# schemat.net
KiCad netlist of a schematic drawn in Altium Designer
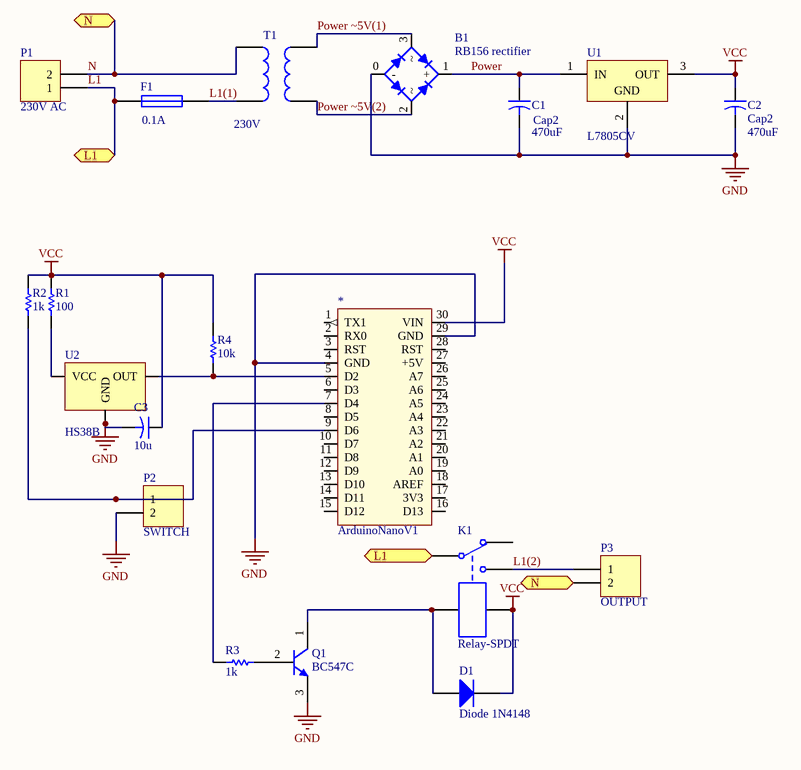
[diagram p0: schemat.SchDoc]

(export (version "E")
  (design (tool "Eeschema 10.0.6"))
  (components
    (comp (ref "*")
      (value "ArduinoNanoV1")
      (footprint "DIP30")
      (libsource (lib "moje komponenty") (part "ArduinoNanoV1"))
    )
    (comp (ref "B1")
      (value "RB156 rectifier")
      (footprint "moje pady:RB15")
      (libsource (lib "moje komponenty") (part "RB156 rectifier"))
    )
    (comp (ref "C1")
      (value "Cap2")
      (footprint "CAPR5-4X5")
      (description "Capacitor")
      (fields (field (name "ALTIUM_VALUE") "470uF") (field (name "PUBLISHER") "Altium Limited"))
      (libsource (lib "Miscellaneous Devices") (part "Cap2"))
    )
    (comp (ref "C2")
      (value "Cap2")
      (footprint "CAPR5-4X5")
      (description "Capacitor")
      (fields (field (name "ALTIUM_VALUE") "470uF") (field (name "PUBLISHER") "Altium Limited"))
      (libsource (lib "Miscellaneous Devices") (part "Cap2"))
    )
    (comp (ref "C3")
      (value "10u")
      (footprint "moje pady:Capacitor")
      (description "Capacitor")
      (fields (field (name "Comment") "Cap2") (field (name "PUBLISHER") "Altium Limited"))
      (libsource (lib "Miscellaneous Devices") (part "Cap2"))
    )
    (comp (ref "D1")
      (value "Diode 1N4148")
      (footprint "DO-35")
      (description "High Conductance Fast Diode")
      (fields (field (name "PUBLISHER") "Altium Limited"))
      (libsource (lib "Miscellaneous Devices") (part "Diode 1N4148"))
    )
    (comp (ref "F1")
      (value "Fuse 1")
      (footprint "PIN-W2/E2.8")
      (description "Fuse")
      (fields (field (name "CURRENT") "0.1A") (field (name "PUBLISHER") "Altium Limited"))
      (libsource (lib "Miscellaneous Devices") (part "Fuse 1"))
    )
    (comp (ref "K1")
      (value "Relay-SPDT")
      (footprint "RELAY_OMRON_G5LE-1")
      (description "Single-Pole Dual-Throw Relay")
      (fields (field (name "PUBLISHER") "Altium Limited"))
      (libsource (lib "Miscellaneous Devices") (part "Relay-SPDT"))
    )
    (comp (ref "P1")
      (value "230V AC")
      (footprint "moje pady:ARK2")
      (description "Header, 2-Pin")
      (fields (field (name "PUBLISHER") "Altium Limited"))
      (libsource (lib "Miscellaneous Connectors") (part "Header 2"))
    )
    (comp (ref "P2")
      (value "SWITCH")
      (footprint "moje pady:ARK2")
      (description "Header, 2-Pin")
      (fields (field (name "PUBLISHER") "Altium Limited"))
      (libsource (lib "") (part "Header 2_1"))
    )
    (comp (ref "P3")
      (value "OUTPUT")
      (footprint "moje pady:ARK2")
      (description "Header, 2-Pin")
      (fields (field (name "PUBLISHER") "Altium Limited"))
      (libsource (lib "") (part "Header 2_1"))
    )
    (comp (ref "Q1")
      (value "BC547C")
      (footprint "ONSC-TO-92-3-29-10_BL")
      (description "Amplifier Transistor, NPN Silicon, 3-Pin TO-92, Bulk Box")
      (fields (field (name "MANUFACTURER") "On Semiconductor"))
      (libsource (lib "ON Semi General Purpose Transistors") (part "BC547C"))
    )
    (comp (ref "R1")
      (value "100")
      (footprint "AXIAL-0.3")
      (description "Resistor")
      (fields (field (name "Comment") "Res1") (field (name "PUBLISHER") "Altium Limited"))
      (libsource (lib "Miscellaneous Devices") (part "Res1"))
    )
    (comp (ref "R2")
      (value "1k")
      (footprint "AXIAL-0.3")
      (description "Resistor")
      (fields (field (name "Comment") "Res1") (field (name "PUBLISHER") "Altium Limited"))
      (libsource (lib "Miscellaneous Devices") (part "Res1"))
    )
    (comp (ref "R3")
      (value "1k")
      (footprint "AXIAL-0.3")
      (description "Resistor")
      (fields (field (name "Comment") "Res1") (field (name "PUBLISHER") "Altium Limited"))
      (libsource (lib "Miscellaneous Devices") (part "Res1"))
    )
    (comp (ref "R4")
      (value "10k")
      (footprint "AXIAL-0.3")
      (description "Resistor")
      (fields (field (name "Comment") "Res1") (field (name "PUBLISHER") "Altium Limited"))
      (libsource (lib "Miscellaneous Devices") (part "Res1"))
    )
    (comp (ref "T1")
      (value "Trans")
      (footprint "moje pady:trafo HAHN 12V 3VA")
      (description "Transformer")
      (fields (field (name "INPUT VOLTAGE") "230V") (field (name "PUBLISHER") "Altium Limited"))
      (libsource (lib "Miscellaneous Devices") (part "Trans"))
    )
    (comp (ref "U1")
      (value "L7805CV")
      (footprint "TO220")
      (description "Positive Voltage Regulator, 5V, 3-Pin TO-220")
      (libsource (lib "STMicroelectronics Power Management Linear Regulator") (part "L7805CV"))
    )
    (comp (ref "U2")
      (value "HS38B")
      (footprint "HS38B_3pin")
      (libsource (lib "moje komponenty") (part "HS38B"))
    )
  )
  (nets
    (net (code "1") (name "/L1") (class "Default")
      (node (ref "F1") (pin "1") (pinfunction "1_1") (pintype "passive"))
      (node (ref "K1") (pin "1") (pinfunction "1_1") (pintype "passive"))
      (node (ref "P1") (pin "1") (pinfunction "1_1") (pintype "passive"))
    )
    (net (code "2") (name "/L1(1)") (class "Default")
      (node (ref "F1") (pin "2") (pinfunction "2_2") (pintype "passive"))
      (node (ref "T1") (pin "2") (pinfunction "2_2") (pintype "passive"))
    )
    (net (code "3") (name "/L1(2)") (class "Default")
      (node (ref "K1") (pin "3") (pinfunction "3_3") (pintype "passive"))
      (node (ref "P3") (pin "1") (pinfunction "1_1") (pintype "passive"))
    )
    (net (code "4") (name "/N") (class "Default")
      (node (ref "P1") (pin "2") (pinfunction "2_2") (pintype "passive"))
      (node (ref "P3") (pin "2") (pinfunction "2_2") (pintype "passive"))
      (node (ref "T1") (pin "1") (pinfunction "1_1") (pintype "passive"))
    )
    (net (code "5") (name "/Power") (class "Default")
      (node (ref "B1") (pin "1") (pinfunction "+_1") (pintype "passive"))
      (node (ref "C1") (pin "1") (pinfunction "1_1") (pintype "passive"))
      (node (ref "U1") (pin "1") (pinfunction "IN_1") (pintype "power_in"))
    )
    (net (code "6") (name "/Power ~5V(1)") (class "Default")
      (node (ref "B1") (pin "3") (pinfunction "~_3") (pintype "passive"))
      (node (ref "T1") (pin "3") (pinfunction "3_3") (pintype "passive"))
    )
    (net (code "7") (name "/Power ~5V(2)") (class "Default")
      (node (ref "B1") (pin "2") (pinfunction "~_2") (pintype "passive"))
      (node (ref "T1") (pin "4") (pinfunction "4_4") (pintype "passive"))
    )
    (net (code "8") (name "GND") (class "Default")
      (node (ref "*") (pin "29") (pinfunction "GND_29") (pintype "passive"))
      (node (ref "*") (pin "4") (pinfunction "GND_4") (pintype "passive"))
      (node (ref "B1") (pin "0") (pinfunction "-_0") (pintype "passive"))
      (node (ref "C1") (pin "2") (pinfunction "2_2") (pintype "passive"))
      (node (ref "C2") (pin "2") (pinfunction "2_2") (pintype "passive"))
      (node (ref "C3") (pin "2") (pinfunction "2_2") (pintype "passive"))
      (node (ref "P2") (pin "2") (pinfunction "2_2") (pintype "passive"))
      (node (ref "Q1") (pin "3") (pinfunction "E_3") (pintype "passive"))
      (node (ref "U1") (pin "2") (pinfunction "GND_2") (pintype "power_in"))
      (node (ref "U2") (pin "2") (pinfunction "GND_2") (pintype "passive"))
    )
    (net (code "9") (name "Net-(*-D2)") (class "Default")
      (node (ref "*") (pin "5") (pinfunction "D2_5") (pintype "bidirectional"))
      (node (ref "R4") (pin "1") (pinfunction "1_1") (pintype "passive"))
      (node (ref "U2") (pin "3") (pinfunction "OUT_3") (pintype "passive"))
    )
    (net (code "10") (name "Net-(*-D4)") (class "Default")
      (node (ref "*") (pin "7") (pinfunction "D4_7") (pintype "bidirectional"))
      (node (ref "R3") (pin "2") (pinfunction "2_2") (pintype "passive"))
    )
    (net (code "11") (name "Net-(*-D6)") (class "Default")
      (node (ref "*") (pin "9") (pinfunction "D6_9") (pintype "bidirectional"))
      (node (ref "P2") (pin "1") (pinfunction "1_1") (pintype "passive"))
      (node (ref "R2") (pin "1") (pinfunction "1_1") (pintype "passive"))
    )
    (net (code "12") (name "Net-(D1-A)") (class "Default")
      (node (ref "D1") (pin "1") (pinfunction "A_1") (pintype "passive"))
      (node (ref "K1") (pin "4") (pinfunction "4_4") (pintype "passive"))
      (node (ref "Q1") (pin "1") (pinfunction "C_1") (pintype "passive"))
    )
    (net (code "13") (name "Net-(Q1-B)") (class "Default")
      (node (ref "Q1") (pin "2") (pinfunction "B_2") (pintype "passive"))
      (node (ref "R3") (pin "1") (pinfunction "1_1") (pintype "passive"))
    )
    (net (code "14") (name "Net-(U2-VCC)") (class "Default")
      (node (ref "R1") (pin "1") (pinfunction "1_1") (pintype "passive"))
      (node (ref "U2") (pin "1") (pinfunction "VCC_1") (pintype "passive"))
    )
    (net (code "15") (name "VCC") (class "Default")
      (node (ref "*") (pin "30") (pinfunction "VIN_30") (pintype "passive"))
      (node (ref "C2") (pin "1") (pinfunction "1_1") (pintype "passive"))
      (node (ref "C3") (pin "1") (pinfunction "1_1") (pintype "passive"))
      (node (ref "D1") (pin "2") (pinfunction "K_2") (pintype "passive"))
      (node (ref "K1") (pin "5") (pinfunction "5_5") (pintype "passive"))
      (node (ref "R1") (pin "2") (pinfunction "2_2") (pintype "passive"))
      (node (ref "R2") (pin "2") (pinfunction "2_2") (pintype "passive"))
      (node (ref "R4") (pin "2") (pinfunction "2_2") (pintype "passive"))
      (node (ref "U1") (pin "3") (pinfunction "OUT_3") (pintype "power_in"))
    )
    (net (code "16") (name "unconnected-(*-+5V-Pad27)") (class "Default")
      (node (ref "*") (pin "27") (pinfunction "+5V_27") (pintype "passive"))
    )
    (net (code "17") (name "unconnected-(*-3V3-Pad17)") (class "Default")
      (node (ref "*") (pin "17") (pinfunction "3V3_17") (pintype "passive"))
    )
    (net (code "18") (name "unconnected-(*-A0-Pad19)") (class "Default")
      (node (ref "*") (pin "19") (pinfunction "A0_19") (pintype "bidirectional"))
    )
    (net (code "19") (name "unconnected-(*-A1-Pad20)") (class "Default")
      (node (ref "*") (pin "20") (pinfunction "A1_20") (pintype "bidirectional"))
    )
    (net (code "20") (name "unconnected-(*-A2-Pad21)") (class "Default")
      (node (ref "*") (pin "21") (pinfunction "A2_21") (pintype "bidirectional"))
    )
    (net (code "21") (name "unconnected-(*-A3-Pad22)") (class "Default")
      (node (ref "*") (pin "22") (pinfunction "A3_22") (pintype "bidirectional"))
    )
    (net (code "22") (name "unconnected-(*-A4-Pad23)") (class "Default")
      (node (ref "*") (pin "23") (pinfunction "A4_23") (pintype "bidirectional"))
    )
    (net (code "23") (name "unconnected-(*-A5-Pad24)") (class "Default")
      (node (ref "*") (pin "24") (pinfunction "A5_24") (pintype "bidirectional"))
    )
    (net (code "24") (name "unconnected-(*-A6-Pad25)") (class "Default")
      (node (ref "*") (pin "25") (pinfunction "A6_25") (pintype "bidirectional"))
    )
    (net (code "25") (name "unconnected-(*-A7-Pad26)") (class "Default")
      (node (ref "*") (pin "26") (pinfunction "A7_26") (pintype "bidirectional"))
    )
    (net (code "26") (name "unconnected-(*-AREF-Pad18)") (class "Default")
      (node (ref "*") (pin "18") (pinfunction "AREF_18") (pintype "passive"))
    )
    (net (code "27") (name "unconnected-(*-D3-Pad6)") (class "Default")
      (node (ref "*") (pin "6") (pinfunction "D3_6") (pintype "bidirectional"))
    )
    (net (code "28") (name "unconnected-(*-D5-Pad8)") (class "Default")
      (node (ref "*") (pin "8") (pinfunction "D5_8") (pintype "bidirectional"))
    )
    (net (code "29") (name "unconnected-(*-D7-Pad10)") (class "Default")
      (node (ref "*") (pin "10") (pinfunction "D7_10") (pintype "bidirectional"))
    )
    (net (code "30") (name "unconnected-(*-D8-Pad11)") (class "Default")
      (node (ref "*") (pin "11") (pinfunction "D8_11") (pintype "bidirectional"))
    )
    (net (code "31") (name "unconnected-(*-D9-Pad12)") (class "Default")
      (node (ref "*") (pin "12") (pinfunction "D9_12") (pintype "bidirectional"))
    )
    (net (code "32") (name "unconnected-(*-D10-Pad13)") (class "Default")
      (node (ref "*") (pin "13") (pinfunction "D10_13") (pintype "bidirectional"))
    )
    (net (code "33") (name "unconnected-(*-D11-Pad14)") (class "Default")
      (node (ref "*") (pin "14") (pinfunction "D11_14") (pintype "bidirectional"))
    )
    (net (code "34") (name "unconnected-(*-D12-Pad15)") (class "Default")
      (node (ref "*") (pin "15") (pinfunction "D12_15") (pintype "bidirectional"))
    )
    (net (code "35") (name "unconnected-(*-D13-Pad16)") (class "Default")
      (node (ref "*") (pin "16") (pinfunction "D13_16") (pintype "bidirectional"))
    )
    (net (code "36") (name "unconnected-(*-RST-Pad3)") (class "Default")
      (node (ref "*") (pin "3") (pinfunction "RST_3") (pintype "bidirectional"))
    )
    (net (code "37") (name "unconnected-(*-RST-Pad28)") (class "Default")
      (node (ref "*") (pin "28") (pinfunction "RST_28") (pintype "bidirectional"))
    )
    (net (code "38") (name "unconnected-(*-RX0-Pad2)") (class "Default")
      (node (ref "*") (pin "2") (pinfunction "RX0_2") (pintype "bidirectional"))
    )
    (net (code "39") (name "unconnected-(*-TX1-Pad1)") (class "Default")
      (node (ref "*") (pin "1") (pinfunction "TX1_1") (pintype "output"))
    )
    (net (code "40") (name "unconnected-(K1-Pad2)") (class "Default")
      (node (ref "K1") (pin "2") (pinfunction "2_2") (pintype "passive"))
    )
  )
)
